# IoTNodeWeatherandWaterAdapterFeb2019v0.net
KiCad netlist of a schematic drawn in EAGLE
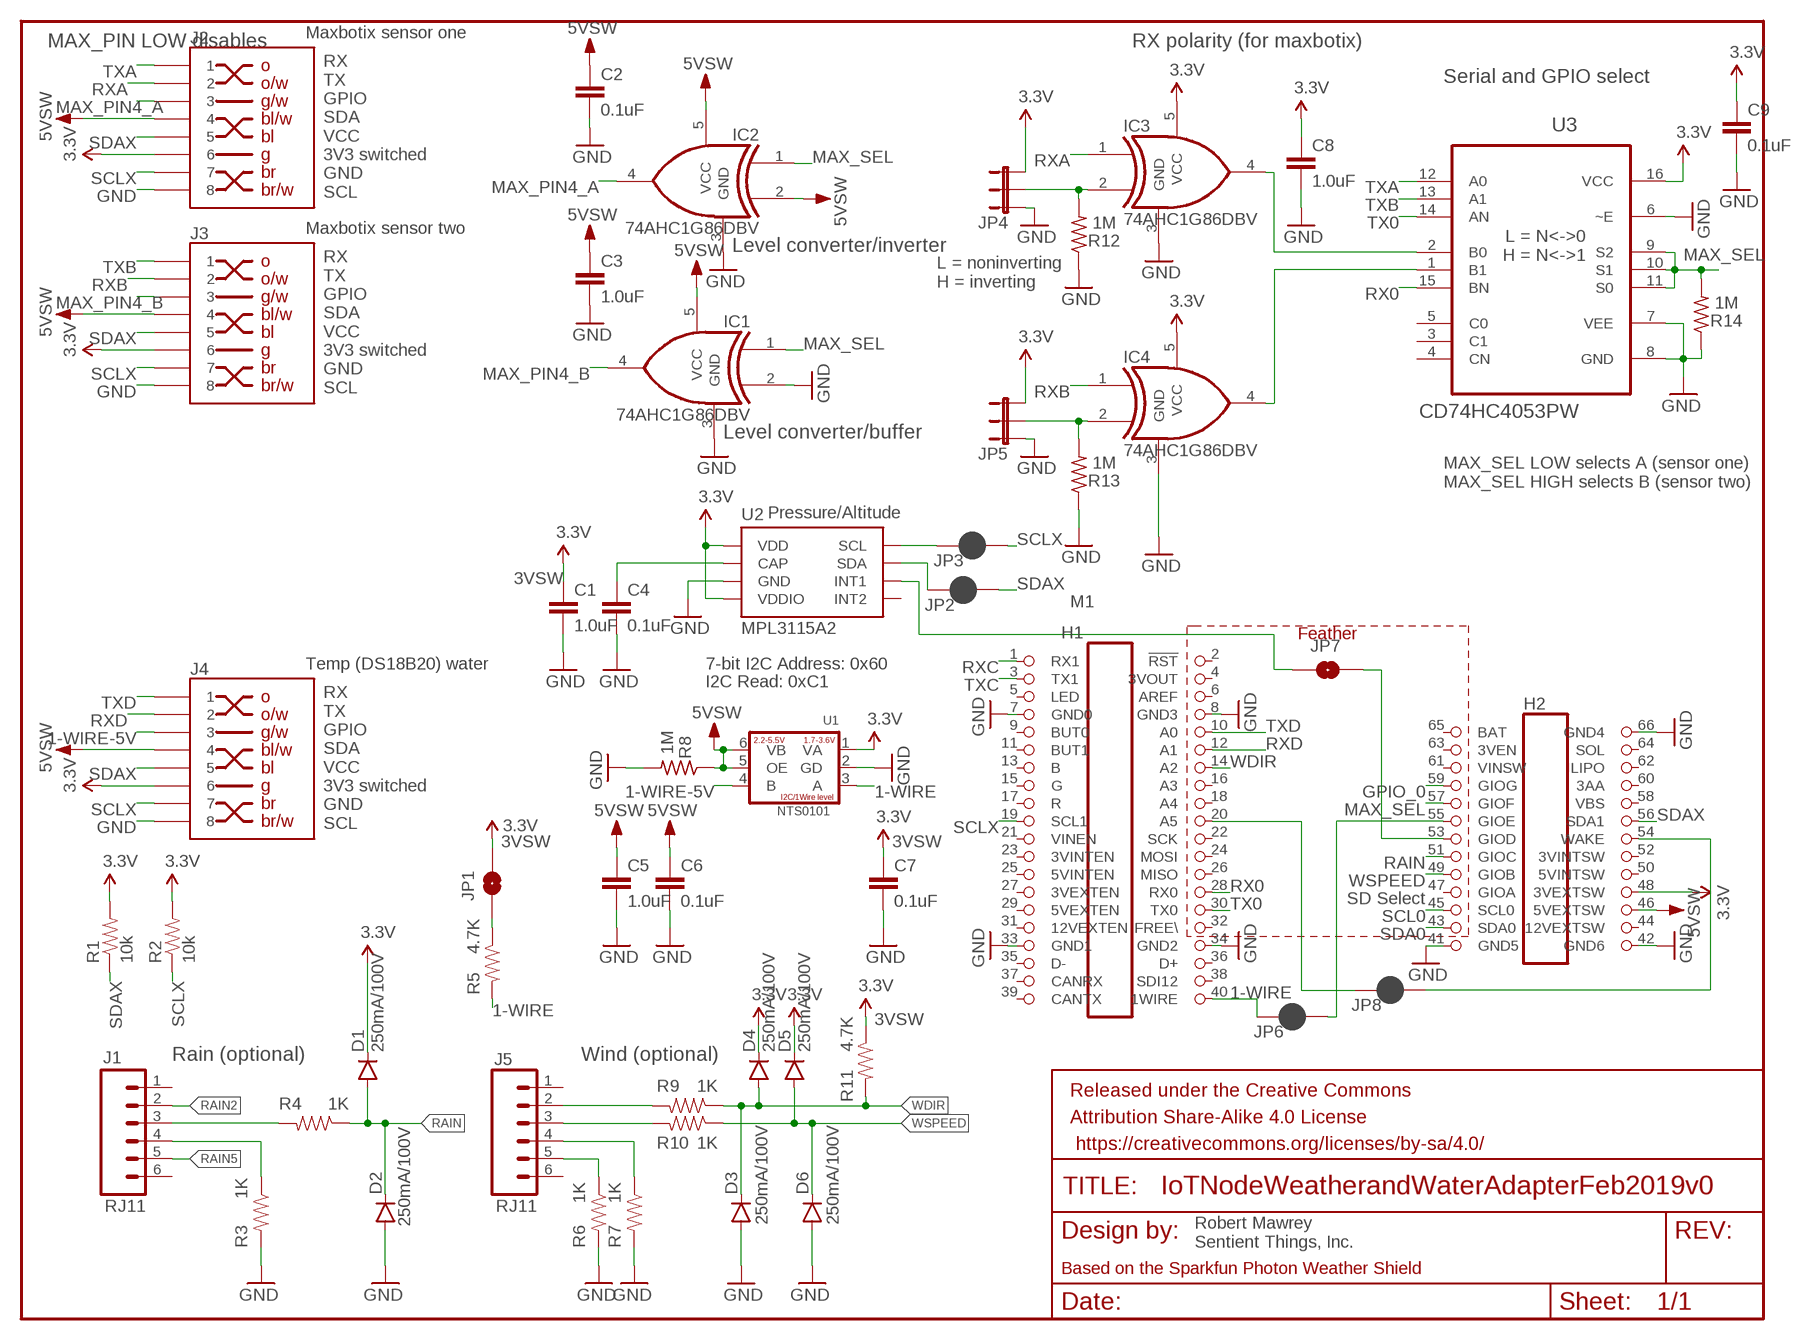
[diagram p0: schematic, sheet 1]

(export (version "E")
  (design (tool "Eeschema 10.0.6"))
  (components
    (comp (ref "C1")
      (value "1.0uF")
      (footprint "eagle-import:0603-CAP")
      (fields (field (name "PARTNO") "CC0603KRX7R8BB105"))
      (libsource (lib "eagle-import") (part "1.0UF-16V-10%(0603)"))
    )
    (comp (ref "C2")
      (value "0.1uF")
      (footprint "eagle-import:0603-CAP")
      (fields (field (name "PARTNO") "C1608X5R1H104K080AA"))
      (libsource (lib "eagle-import") (part "0.1UF-25V(+80/-20%)(0603)"))
    )
    (comp (ref "C3")
      (value "1.0uF")
      (footprint "eagle-import:0603-CAP")
      (fields (field (name "PARTNO") "CC0603KRX7R8BB105"))
      (libsource (lib "eagle-import") (part "1.0UF-16V-10%(0603)"))
    )
    (comp (ref "C4")
      (value "0.1uF")
      (footprint "eagle-import:0603-CAP")
      (fields (field (name "PARTNO") "C1608X5R1H104K080AA"))
      (libsource (lib "eagle-import") (part "0.1UF-25V(+80/-20%)(0603)"))
    )
    (comp (ref "C5")
      (value "1.0uF")
      (footprint "eagle-import:0603-CAP")
      (fields (field (name "PARTNO") "CC0603KRX7R8BB105"))
      (libsource (lib "eagle-import") (part "1.0UF-16V-10%(0603)"))
    )
    (comp (ref "C6")
      (value "0.1uF")
      (footprint "eagle-import:0603-CAP")
      (fields (field (name "PARTNO") "C1608X5R1H104K080AA"))
      (libsource (lib "eagle-import") (part "0.1UF-25V(+80/-20%)(0603)"))
    )
    (comp (ref "C7")
      (value "0.1uF")
      (footprint "eagle-import:0603-CAP")
      (fields (field (name "PARTNO") "C1608X5R1H104K080AA"))
      (libsource (lib "eagle-import") (part "0.1UF-25V(+80/-20%)(0603)"))
    )
    (comp (ref "C8")
      (value "1.0uF")
      (footprint "eagle-import:0603-CAP")
      (fields (field (name "PARTNO") "CC0603KRX7R8BB105"))
      (libsource (lib "eagle-import") (part "1.0UF-16V-10%(0603)"))
    )
    (comp (ref "C9")
      (value "0.1uF")
      (footprint "eagle-import:0603-CAP")
      (fields (field (name "PARTNO") "C1608X5R1H104K080AA"))
      (libsource (lib "eagle-import") (part "0.1UF-25V(+80/-20%)(0603)"))
    )
    (comp (ref "D1")
      (value "250mA/100V")
      (footprint "eagle-import:SOD-323")
      (fields (field (name "PARTNO") "BAS16J,135"))
      (libsource (lib "eagle-import") (part "DIODEBAS16"))
    )
    (comp (ref "D2")
      (value "250mA/100V")
      (footprint "eagle-import:SOD-323")
      (fields (field (name "PARTNO") "BAS16J,135"))
      (libsource (lib "eagle-import") (part "DIODEBAS16"))
    )
    (comp (ref "D3")
      (value "250mA/100V")
      (footprint "eagle-import:SOD-323")
      (fields (field (name "PARTNO") "BAS16J,135"))
      (libsource (lib "eagle-import") (part "DIODEBAS16"))
    )
    (comp (ref "D4")
      (value "250mA/100V")
      (footprint "eagle-import:SOD-323")
      (fields (field (name "PARTNO") "BAS16J,135"))
      (libsource (lib "eagle-import") (part "DIODEBAS16"))
    )
    (comp (ref "D5")
      (value "250mA/100V")
      (footprint "eagle-import:SOD-323")
      (fields (field (name "PARTNO") "BAS16J,135"))
      (libsource (lib "eagle-import") (part "DIODEBAS16"))
    )
    (comp (ref "D6")
      (value "250mA/100V")
      (footprint "eagle-import:SOD-323")
      (fields (field (name "PARTNO") "BAS16J,135"))
      (libsource (lib "eagle-import") (part "DIODEBAS16"))
    )
    (comp (ref "FRAME1")
      (value "FRAME-LETTER")
      (footprint "eagle-import:CREATIVE_COMMONS")
      (fields (field (name "PARTNO") "DNP"))
      (libsource (lib "eagle-import") (part "FRAME-LETTER"))
    )
    (comp (ref "H1")
      (value "IOTNODE2X20PLACEMENT")
      (footprint "eagle-import:2X20PLACEMENT")
      (libsource (lib "eagle-import") (part "IOTNODE2X20PLACEMENT"))
    )
    (comp (ref "H2")
      (value "IOTNODE2X13PLACEMENT")
      (footprint "eagle-import:2X13PLACEMENT")
      (libsource (lib "eagle-import") (part "IOTNODE2X13PLACEMENT"))
    )
    (comp (ref "IC1")
      (value "74AHC1G86DBV")
      (footprint "eagle-import:SOT23-5")
      (fields (field (name "PARTNO") "SN74AHC1G86DBVR"))
      (libsource (lib "eagle-import") (part "741G86DBVAHC"))
    )
    (comp (ref "IC2")
      (value "74AHC1G86DBV")
      (footprint "eagle-import:SOT23-5")
      (fields (field (name "PARTNO") "SN74AHC1G86DBVR"))
      (libsource (lib "eagle-import") (part "741G86DBVAHC"))
    )
    (comp (ref "IC3")
      (value "74AHC1G86DBV")
      (footprint "eagle-import:SOT23-5")
      (fields (field (name "PARTNO") "SN74AHC1G86DBVR"))
      (libsource (lib "eagle-import") (part "741G86DBVAHC"))
    )
    (comp (ref "IC4")
      (value "74AHC1G86DBV")
      (footprint "eagle-import:SOT23-5")
      (fields (field (name "PARTNO") "SN74AHC1G86DBVR"))
      (libsource (lib "eagle-import") (part "741G86DBVAHC"))
    )
    (comp (ref "J1")
      (value "RJ11")
      (footprint "eagle-import:RJ11-6")
      (fields (field (name "PARTNO") "5555165-1"))
      (libsource (lib "eagle-import") (part "RJ11-6PTH"))
    )
    (comp (ref "J2")
      (value "RJ45-8-UP")
      (footprint "eagle-import:RJHSE-5080")
      (fields (field (name "PARTNO") "RJHSE-5080"))
      (libsource (lib "eagle-import") (part "RJ45-8-UP"))
    )
    (comp (ref "J3")
      (value "RJ45-8-UP")
      (footprint "eagle-import:RJHSE-5080")
      (fields (field (name "PARTNO") "RJHSE-5080"))
      (libsource (lib "eagle-import") (part "RJ45-8-UP"))
    )
    (comp (ref "J4")
      (value "RJ45-8-UP")
      (footprint "eagle-import:RJHSE-5080")
      (fields (field (name "PARTNO") "RJHSE-5080"))
      (libsource (lib "eagle-import") (part "RJ45-8-UP"))
    )
    (comp (ref "J5")
      (value "RJ11")
      (footprint "eagle-import:RJ11-6")
      (fields (field (name "PARTNO") "5555165-1"))
      (libsource (lib "eagle-import") (part "RJ11-6PTH"))
    )
    (comp (ref "JP1")
      (value "JUMPER-PAD-2-NOYES_SILK")
      (footprint "eagle-import:PAD-JUMPER-2-NO_YES_SILK")
      (fields (field (name "PARTNO") "DNP"))
      (libsource (lib "eagle-import") (part "JUMPER-PAD-2-NOYES_SILK"))
    )
    (comp (ref "JP2")
      (value "JUMPER-SMT_2_NC_PASTE_NO-SILK")
      (footprint "eagle-import:SMT-JUMPER_2_NC_PASTE_NO-SILK")
      (fields (field (name "PARTNO") "DNP"))
      (libsource (lib "eagle-import") (part "JUMPER-SMT_2_NC_PASTE_NO-SILK"))
    )
    (comp (ref "JP3")
      (value "JUMPER-SMT_2_NC_PASTE_NO-SILK")
      (footprint "eagle-import:SMT-JUMPER_2_NC_PASTE_NO-SILK")
      (fields (field (name "PARTNO") "DNP"))
      (libsource (lib "eagle-import") (part "JUMPER-SMT_2_NC_PASTE_NO-SILK"))
    )
    (comp (ref "JP4")
      (value "JUMPER-3LOCK")
      (footprint "eagle-import:1X03_LOCK")
      (fields (field (name "PARTNO") "68000-103HLF"))
      (libsource (lib "eagle-import") (part "JUMPER-3LOCK"))
    )
    (comp (ref "JP5")
      (value "JUMPER-3LOCK")
      (footprint "eagle-import:1X03_LOCK")
      (fields (field (name "PARTNO") "68000-103HLF"))
      (libsource (lib "eagle-import") (part "JUMPER-3LOCK"))
    )
    (comp (ref "JP6")
      (value "JUMPER-SMT_2_NC_PASTE_NO-SILK")
      (footprint "eagle-import:SMT-JUMPER_2_NC_PASTE_NO-SILK")
      (fields (field (name "PARTNO") "DNP"))
      (libsource (lib "eagle-import") (part "JUMPER-SMT_2_NC_PASTE_NO-SILK"))
    )
    (comp (ref "JP7")
      (value "JUMPER-SMT_2_NO_NO-SILK")
      (footprint "eagle-import:SMT-JUMPER_2_NO_NO-SILK")
      (fields (field (name "PARTNO") "DNP"))
      (libsource (lib "eagle-import") (part "JUMPER-SMT_2_NO_NO-SILK"))
    )
    (comp (ref "JP8")
      (value "JUMPER-SMT_2_NC_PASTE_NO-SILK")
      (footprint "eagle-import:SMT-JUMPER_2_NC_PASTE_NO-SILK")
      (fields (field (name "PARTNO") "DNP"))
      (libsource (lib "eagle-import") (part "JUMPER-SMT_2_NC_PASTE_NO-SILK"))
    )
    (comp (ref "M1")
      (value "IOTNODEFEATHERWING")
      (footprint "eagle-import:IOTNODEFEATHERWING")
      (fields (field (name "PARTNO") "DNP"))
      (libsource (lib "eagle-import") (part "IOTNODEFEATHERWING"))
    )
    (comp (ref "R1")
      (value "10k")
      (footprint "eagle-import:0603-RES")
      (fields (field (name "PARTNO") "ERJ-3GEYJ103V"))
      (libsource (lib "eagle-import") (part "RESISTOR0603-RES"))
    )
    (comp (ref "R2")
      (value "10k")
      (footprint "eagle-import:0603-RES")
      (fields (field (name "PARTNO") "ERJ-3GEYJ103V"))
      (libsource (lib "eagle-import") (part "RESISTOR0603-RES"))
    )
    (comp (ref "R3")
      (value "1K")
      (footprint "eagle-import:0603-RES")
      (fields (field (name "PARTNO") "RC0603JR-071KL"))
      (libsource (lib "eagle-import") (part "1KOHM-1/10W-1%(0603)"))
    )
    (comp (ref "R4")
      (value "1K")
      (footprint "eagle-import:0603-RES")
      (fields (field (name "PARTNO") "RC0603JR-071KL"))
      (libsource (lib "eagle-import") (part "1KOHM-1/10W-1%(0603)"))
    )
    (comp (ref "R5")
      (value "4.7K")
      (footprint "eagle-import:0603-RES")
      (fields (field (name "PARTNO") "RC0603JR-074K7L"))
      (libsource (lib "eagle-import") (part "4.7KOHM-1/10W-1%(0603)"))
    )
    (comp (ref "R6")
      (value "1K")
      (footprint "eagle-import:0603-RES")
      (fields (field (name "PARTNO") "RC0603JR-071KL"))
      (libsource (lib "eagle-import") (part "1KOHM-1/10W-1%(0603)"))
    )
    (comp (ref "R7")
      (value "1K")
      (footprint "eagle-import:0603-RES")
      (fields (field (name "PARTNO") "RC0603JR-071KL"))
      (libsource (lib "eagle-import") (part "1KOHM-1/10W-1%(0603)"))
    )
    (comp (ref "R8")
      (value "1M")
      (footprint "eagle-import:0603")
      (fields (field (name "PARTNO") "RC0603FR-071ML"))
      (libsource (lib "eagle-import") (part "R_0603"))
    )
    (comp (ref "R9")
      (value "1K")
      (footprint "eagle-import:0603-RES")
      (fields (field (name "PARTNO") "RC0603JR-071KL"))
      (libsource (lib "eagle-import") (part "1KOHM-1/10W-1%(0603)"))
    )
    (comp (ref "R10")
      (value "1K")
      (footprint "eagle-import:0603-RES")
      (fields (field (name "PARTNO") "RC0603JR-071KL"))
      (libsource (lib "eagle-import") (part "1KOHM-1/10W-1%(0603)"))
    )
    (comp (ref "R11")
      (value "4.7K")
      (footprint "eagle-import:0603-RES")
      (fields (field (name "PARTNO") "RC0603JR-074K7L"))
      (libsource (lib "eagle-import") (part "4.7KOHM-1/10W-1%(0603)"))
    )
    (comp (ref "R12")
      (value "1M")
      (footprint "eagle-import:0603")
      (fields (field (name "PARTNO") "RC0603FR-071ML"))
      (libsource (lib "eagle-import") (part "R_0603"))
    )
    (comp (ref "R13")
      (value "1M")
      (footprint "eagle-import:0603")
      (fields (field (name "PARTNO") "RC0603FR-071ML"))
      (libsource (lib "eagle-import") (part "R_0603"))
    )
    (comp (ref "R14")
      (value "1M")
      (footprint "eagle-import:0603")
      (fields (field (name "PARTNO") "RC0603FR-071ML"))
      (libsource (lib "eagle-import") (part "R_0603"))
    )
    (comp (ref "U1")
      (value "NTS0101")
      (footprint "eagle-import:SOT363_PHILIPS")
      (fields (field (name "PARTNO") "NTS0101GW,125"))
      (libsource (lib "eagle-import") (part "NTS0101-SC-88"))
    )
    (comp (ref "U2")
      (value "MPL3115A2")
      (footprint "eagle-import:LGA-8-5X3")
      (libsource (lib "eagle-import") (part "MPL3115A2"))
    )
    (comp (ref "U3")
      (value "CD74HC4053PW")
      (footprint "eagle-import:SOP65P640X120-16N")
      (fields (field (name "PARTNO") "74HC4053PW,118"))
      (libsource (lib "eagle-import") (part "CD74HC4053PW"))
    )
  )
  (nets
    (net (code "1") (name "/1-WIRE") (class "Default")
      (node (ref "JP6") (pin "2") (pinfunction "2_2") (pintype "passive"))
      (node (ref "M1") (pin "40") (pinfunction "1WIRE_40") (pintype "bidirectional"))
      (node (ref "R5") (pin "2") (pinfunction "2_2") (pintype "passive"))
      (node (ref "U1") (pin "3") (pinfunction "A_3") (pintype "bidirectional"))
    )
    (net (code "2") (name "/1-WIRE-5V") (class "Default")
      (node (ref "J4") (pin "3") (pinfunction "3_3") (pintype "bidirectional"))
      (node (ref "U1") (pin "4") (pinfunction "B_4") (pintype "bidirectional"))
    )
    (net (code "3") (name "/GPIO_0") (class "Default")
      (node (ref "M1") (pin "59") (pinfunction "GIOG_59") (pintype "bidirectional"))
    )
    (net (code "4") (name "/MAX_PIN4_A") (class "Default")
      (node (ref "IC2") (pin "4") (pinfunction "O_4") (pintype "output"))
      (node (ref "J2") (pin "3") (pinfunction "3_3") (pintype "bidirectional"))
    )
    (net (code "5") (name "/MAX_PIN4_B") (class "Default")
      (node (ref "IC1") (pin "4") (pinfunction "O_4") (pintype "output"))
      (node (ref "J3") (pin "3") (pinfunction "3_3") (pintype "bidirectional"))
    )
    (net (code "6") (name "/MAX_SEL") (class "Default")
      (node (ref "IC1") (pin "1") (pinfunction "I0_1") (pintype "input"))
      (node (ref "IC2") (pin "1") (pinfunction "I0_1") (pintype "input"))
      (node (ref "M1") (pin "57") (pinfunction "GIOF_57") (pintype "bidirectional"))
      (node (ref "R14") (pin "2") (pinfunction "2_2") (pintype "passive"))
      (node (ref "U3") (pin "10") (pinfunction "S1_10") (pintype "input"))
      (node (ref "U3") (pin "11") (pinfunction "S0_11") (pintype "input"))
      (node (ref "U3") (pin "9") (pinfunction "S2_9") (pintype "input"))
    )
    (net (code "7") (name "/RX0") (class "Default")
      (node (ref "M1") (pin "28") (pinfunction "RX0_28") (pintype "bidirectional"))
      (node (ref "U3") (pin "15") (pinfunction "BN_15") (pintype "output"))
    )
    (net (code "8") (name "/RXA") (class "Default")
      (node (ref "IC3") (pin "1") (pinfunction "I0_1") (pintype "input"))
      (node (ref "J2") (pin "2") (pinfunction "2_2") (pintype "bidirectional"))
    )
    (net (code "9") (name "/RXB") (class "Default")
      (node (ref "IC4") (pin "1") (pinfunction "I0_1") (pintype "input"))
      (node (ref "J3") (pin "2") (pinfunction "2_2") (pintype "bidirectional"))
    )
    (net (code "10") (name "/RXC") (class "Default")
      (node (ref "M1") (pin "1") (pinfunction "RX1_1") (pintype "bidirectional"))
    )
    (net (code "11") (name "/RXD") (class "Default")
      (node (ref "J4") (pin "2") (pinfunction "2_2") (pintype "bidirectional"))
      (node (ref "M1") (pin "12") (pinfunction "A1_12") (pintype "bidirectional"))
    )
    (net (code "12") (name "/SCL0") (class "Default")
      (node (ref "M1") (pin "45") (pinfunction "SCL0_45") (pintype "bidirectional"))
    )
    (net (code "13") (name "/SCLX") (class "Default")
      (node (ref "J2") (pin "7") (pinfunction "7_7") (pintype "bidirectional"))
      (node (ref "J3") (pin "7") (pinfunction "7_7") (pintype "bidirectional"))
      (node (ref "J4") (pin "7") (pinfunction "7_7") (pintype "bidirectional"))
      (node (ref "JP3") (pin "1") (pinfunction "1_1") (pintype "passive"))
      (node (ref "M1") (pin "19") (pinfunction "SCL1_19") (pintype "bidirectional"))
      (node (ref "R2") (pin "1") (pinfunction "1_1") (pintype "passive"))
    )
    (net (code "14") (name "/SDA0") (class "Default")
      (node (ref "M1") (pin "43") (pinfunction "SDA0_43") (pintype "bidirectional"))
    )
    (net (code "15") (name "/SDAX") (class "Default")
      (node (ref "J2") (pin "5") (pinfunction "5_5") (pintype "bidirectional"))
      (node (ref "J3") (pin "5") (pinfunction "5_5") (pintype "bidirectional"))
      (node (ref "J4") (pin "5") (pinfunction "5_5") (pintype "bidirectional"))
      (node (ref "JP2") (pin "1") (pinfunction "1_1") (pintype "passive"))
      (node (ref "M1") (pin "56") (pinfunction "SDA1_56") (pintype "bidirectional"))
      (node (ref "R1") (pin "1") (pinfunction "1_1") (pintype "passive"))
    )
    (net (code "16") (name "/TX0") (class "Default")
      (node (ref "M1") (pin "30") (pinfunction "TX0_30") (pintype "bidirectional"))
      (node (ref "U3") (pin "14") (pinfunction "AN_14") (pintype "output"))
    )
    (net (code "17") (name "/TXA") (class "Default")
      (node (ref "J2") (pin "1") (pinfunction "1_1") (pintype "bidirectional"))
      (node (ref "U3") (pin "12") (pinfunction "A0_12") (pintype "output"))
    )
    (net (code "18") (name "/TXB") (class "Default")
      (node (ref "J3") (pin "1") (pinfunction "1_1") (pintype "bidirectional"))
      (node (ref "U3") (pin "13") (pinfunction "A1_13") (pintype "output"))
    )
    (net (code "19") (name "/TXC") (class "Default")
      (node (ref "M1") (pin "3") (pinfunction "TX1_3") (pintype "bidirectional"))
    )
    (net (code "20") (name "/TXD") (class "Default")
      (node (ref "J4") (pin "1") (pinfunction "1_1") (pintype "bidirectional"))
      (node (ref "M1") (pin "10") (pinfunction "A0_10") (pintype "bidirectional"))
    )
    (net (code "21") (name "3.3V") (class "Default")
      (node (ref "C1") (pin "1") (pinfunction "1_1") (pintype "passive"))
      (node (ref "C7") (pin "1") (pinfunction "1_1") (pintype "passive"))
      (node (ref "C8") (pin "1") (pinfunction "1_1") (pintype "passive"))
      (node (ref "C9") (pin "1") (pinfunction "1_1") (pintype "passive"))
      (node (ref "D1") (pin "C") (pinfunction "C_C") (pintype "passive"))
      (node (ref "D4") (pin "C") (pinfunction "C_C") (pintype "passive"))
      (node (ref "D5") (pin "C") (pinfunction "C_C") (pintype "passive"))
      (node (ref "IC3") (pin "5") (pinfunction "VCC_5") (pintype "bidirectional"))
      (node (ref "IC4") (pin "5") (pinfunction "VCC_5") (pintype "bidirectional"))
      (node (ref "J2") (pin "6") (pinfunction "6_6") (pintype "bidirectional"))
      (node (ref "J3") (pin "6") (pinfunction "6_6") (pintype "bidirectional"))
      (node (ref "J4") (pin "6") (pinfunction "6_6") (pintype "bidirectional"))
      (node (ref "JP1") (pin "2") (pinfunction "2_2") (pintype "passive"))
      (node (ref "JP4") (pin "3") (pinfunction "3_3") (pintype "passive"))
      (node (ref "JP5") (pin "3") (pinfunction "3_3") (pintype "passive"))
      (node (ref "M1") (pin "48") (pinfunction "3VEXTSW_48") (pintype "bidirectional"))
      (node (ref "R1") (pin "2") (pinfunction "2_2") (pintype "passive"))
      (node (ref "R11") (pin "1") (pinfunction "1_1") (pintype "passive"))
      (node (ref "R2") (pin "2") (pinfunction "2_2") (pintype "passive"))
      (node (ref "U1") (pin "1") (pinfunction "VA_1") (pintype "bidirectional"))
      (node (ref "U2") (pin "1") (pinfunction "VDD_1") (pintype "power_in"))
      (node (ref "U2") (pin "4") (pinfunction "VDDIO_4") (pintype "power_in"))
      (node (ref "U3") (pin "16") (pinfunction "VCC_16") (pintype "power_in"))
    )
    (net (code "22") (name "5VSW") (class "Default")
      (node (ref "C2") (pin "1") (pinfunction "1_1") (pintype "passive"))
      (node (ref "C3") (pin "1") (pinfunction "1_1") (pintype "passive"))
      (node (ref "C5") (pin "1") (pinfunction "1_1") (pintype "passive"))
      (node (ref "C6") (pin "1") (pinfunction "1_1") (pintype "passive"))
      (node (ref "IC1") (pin "5") (pinfunction "VCC_5") (pintype "bidirectional"))
      (node (ref "IC2") (pin "2") (pinfunction "I1_2") (pintype "input"))
      (node (ref "IC2") (pin "5") (pinfunction "VCC_5") (pintype "bidirectional"))
      (node (ref "J2") (pin "4") (pinfunction "4_4") (pintype "bidirectional"))
      (node (ref "J3") (pin "4") (pinfunction "4_4") (pintype "bidirectional"))
      (node (ref "J4") (pin "4") (pinfunction "4_4") (pintype "bidirectional"))
      (node (ref "M1") (pin "46") (pinfunction "5VEXTSW_46") (pintype "bidirectional"))
      (node (ref "R8") (pin "1") (pinfunction "1_1") (pintype "passive"))
      (node (ref "U1") (pin "5") (pinfunction "OE_5") (pintype "bidirectional"))
      (node (ref "U1") (pin "6") (pinfunction "VB_6") (pintype "bidirectional"))
    )
    (net (code "23") (name "GND") (class "Default")
      (node (ref "C1") (pin "2") (pinfunction "2_2") (pintype "passive"))
      (node (ref "C2") (pin "2") (pinfunction "2_2") (pintype "passive"))
      (node (ref "C3") (pin "2") (pinfunction "2_2") (pintype "passive"))
      (node (ref "C4") (pin "2") (pinfunction "2_2") (pintype "passive"))
      (node (ref "C5") (pin "2") (pinfunction "2_2") (pintype "passive"))
      (node (ref "C6") (pin "2") (pinfunction "2_2") (pintype "passive"))
      (node (ref "C7") (pin "2") (pinfunction "2_2") (pintype "passive"))
      (node (ref "C8") (pin "2") (pinfunction "2_2") (pintype "passive"))
      (node (ref "C9") (pin "2") (pinfunction "2_2") (pintype "passive"))
      (node (ref "D2") (pin "A") (pinfunction "A_A") (pintype "passive"))
      (node (ref "D3") (pin "A") (pinfunction "A_A") (pintype "passive"))
      (node (ref "D6") (pin "A") (pinfunction "A_A") (pintype "passive"))
      (node (ref "IC1") (pin "2") (pinfunction "I1_2") (pintype "input"))
      (node (ref "IC1") (pin "3") (pinfunction "GND_3") (pintype "bidirectional"))
      (node (ref "IC2") (pin "3") (pinfunction "GND_3") (pintype "bidirectional"))
      (node (ref "IC3") (pin "3") (pinfunction "GND_3") (pintype "bidirectional"))
      (node (ref "IC4") (pin "3") (pinfunction "GND_3") (pintype "bidirectional"))
      (node (ref "J2") (pin "8") (pinfunction "8_8") (pintype "bidirectional"))
      (node (ref "J3") (pin "8") (pinfunction "8_8") (pintype "bidirectional"))
      (node (ref "J4") (pin "8") (pinfunction "8_8") (pintype "bidirectional"))
      (node (ref "JP4") (pin "1") (pinfunction "1_1") (pintype "passive"))
      (node (ref "JP5") (pin "1") (pinfunction "1_1") (pintype "passive"))
      (node (ref "M1") (pin "33") (pinfunction "GND1_33") (pintype "bidirectional"))
      (node (ref "M1") (pin "34") (pinfunction "GND2_34") (pintype "bidirectional"))
      (node (ref "M1") (pin "41") (pinfunction "GND5_41") (pintype "bidirectional"))
      (node (ref "M1") (pin "42") (pinfunction "GND6_42") (pintype "bidirectional"))
      (node (ref "M1") (pin "66") (pinfunction "GND4_66") (pintype "bidirectional"))
      (node (ref "M1") (pin "7") (pinfunction "GND0_7") (pintype "bidirectional"))
      (node (ref "M1") (pin "8") (pinfunction "GND3_8") (pintype "bidirectional"))
      (node (ref "R12") (pin "1") (pinfunction "1_1") (pintype "passive"))
      (node (ref "R13") (pin "1") (pinfunction "1_1") (pintype "passive"))
      (node (ref "R14") (pin "1") (pinfunction "1_1") (pintype "passive"))
      (node (ref "R3") (pin "2") (pinfunction "2_2") (pintype "passive"))
      (node (ref "R6") (pin "2") (pinfunction "2_2") (pintype "passive"))
      (node (ref "R7") (pin "2") (pinfunction "2_2") (pintype "passive"))
      (node (ref "R8") (pin "2") (pinfunction "2_2") (pintype "passive"))
      (node (ref "U1") (pin "2") (pinfunction "GD_2") (pintype "bidirectional"))
      (node (ref "U2") (pin "3") (pinfunction "GND_3") (pintype "power_in"))
      (node (ref "U3") (pin "6") (pinfunction "~{E}_6") (pintype "input"))
      (node (ref "U3") (pin "7") (pinfunction "VEE_7") (pintype "power_in"))
      (node (ref "U3") (pin "8") (pinfunction "GND_8") (pintype "passive"))
    )
    (net (code "24") (name "Net-(IC3-I1)") (class "Default")
      (node (ref "IC3") (pin "2") (pinfunction "I1_2") (pintype "input"))
      (node (ref "JP4") (pin "2") (pinfunction "2_2") (pintype "passive"))
      (node (ref "R12") (pin "2") (pinfunction "2_2") (pintype "passive"))
    )
    (net (code "25") (name "Net-(IC3-O)") (class "Default")
      (node (ref "IC3") (pin "4") (pinfunction "O_4") (pintype "output"))
      (node (ref "U3") (pin "2") (pinfunction "B0_2") (pintype "output"))
    )
    (net (code "26") (name "Net-(IC4-I1)") (class "Default")
      (node (ref "IC4") (pin "2") (pinfunction "I1_2") (pintype "input"))
      (node (ref "JP5") (pin "2") (pinfunction "2_2") (pintype "passive"))
      (node (ref "R13") (pin "2") (pinfunction "2_2") (pintype "passive"))
    )
    (net (code "27") (name "Net-(IC4-O)") (class "Default")
      (node (ref "IC4") (pin "4") (pinfunction "O_4") (pintype "output"))
      (node (ref "U3") (pin "1") (pinfunction "B1_1") (pintype "output"))
    )
    (net (code "28") (name "Net-(J1-Pad3)") (class "Default")
      (node (ref "J1") (pin "3") (pinfunction "3_3") (pintype "passive"))
      (node (ref "R4") (pin "2") (pinfunction "2_2") (pintype "passive"))
    )
    (net (code "29") (name "Net-(J1-Pad4)") (class "Default")
      (node (ref "J1") (pin "4") (pinfunction "4_4") (pintype "passive"))
      (node (ref "R3") (pin "1") (pinfunction "1_1") (pintype "passive"))
    )
    (net (code "30") (name "Net-(J5-Pad2)") (class "Default")
      (node (ref "J5") (pin "2") (pinfunction "2_2") (pintype "passive"))
      (node (ref "R9") (pin "2") (pinfunction "2_2") (pintype "passive"))
    )
    (net (code "31") (name "Net-(J5-Pad3)") (class "Default")
      (node (ref "J5") (pin "3") (pinfunction "3_3") (pintype "passive"))
      (node (ref "R10") (pin "2") (pinfunction "2_2") (pintype "passive"))
    )
    (net (code "32") (name "Net-(J5-Pad4)") (class "Default")
      (node (ref "J5") (pin "4") (pinfunction "4_4") (pintype "passive"))
      (node (ref "R7") (pin "1") (pinfunction "1_1") (pintype "passive"))
    )
    (net (code "33") (name "Net-(J5-Pad5)") (class "Default")
      (node (ref "J5") (pin "5") (pinfunction "5_5") (pintype "passive"))
      (node (ref "R6") (pin "1") (pinfunction "1_1") (pintype "passive"))
    )
    (net (code "34") (name "Net-(JP1-Pad1)") (class "Default")
      (node (ref "JP1") (pin "1") (pinfunction "1_1") (pintype "passive"))
      (node (ref "R5") (pin "1") (pinfunction "1_1") (pintype "passive"))
    )
    (net (code "35") (name "Net-(M1-A5)") (class "Default")
      (node (ref "JP8") (pin "2") (pinfunction "2_2") (pintype "passive"))
      (node (ref "M1") (pin "20") (pinfunction "A5_20") (pintype "bidirectional"))
    )
    (net (code "36") (name "Net-(M1-GIOD)") (class "Default")
      (node (ref "JP7") (pin "2") (pinfunction "2_2") (pintype "passive"))
      (node (ref "M1") (pin "53") (pinfunction "GIOD_53") (pintype "bidirectional"))
    )
    (net (code "37") (name "Net-(M1-GIOE)") (class "Default")
      (node (ref "JP6") (pin "1") (pinfunction "1_1") (pintype "passive"))
      (node (ref "M1") (pin "55") (pinfunction "GIOE_55") (pintype "bidirectional"))
    )
    (net (code "38") (name "Net-(M1-WAKE)") (class "Default")
      (node (ref "JP8") (pin "1") (pinfunction "1_1") (pintype "passive"))
      (node (ref "M1") (pin "54") (pinfunction "WAKE_54") (pintype "bidirectional"))
    )
    (net (code "39") (name "Net-(U2-CAP)") (class "Default")
      (node (ref "C4") (pin "1") (pinfunction "1_1") (pintype "passive"))
      (node (ref "U2") (pin "2") (pinfunction "CAP_2") (pintype "power_in"))
    )
    (net (code "40") (name "Net-(U2-INT1)") (class "Default")
      (node (ref "JP7") (pin "1") (pinfunction "1_1") (pintype "passive"))
      (node (ref "U2") (pin "6") (pinfunction "INT1_6") (pintype "output"))
    )
    (net (code "41") (name "Net-(U2-SCL)") (class "Default")
      (node (ref "JP3") (pin "2") (pinfunction "2_2") (pintype "passive"))
      (node (ref "U2") (pin "8") (pinfunction "SCL_8") (pintype "bidirectional"))
    )
    (net (code "42") (name "Net-(U2-SDA)") (class "Default")
      (node (ref "JP2") (pin "2") (pinfunction "2_2") (pintype "passive"))
      (node (ref "U2") (pin "7") (pinfunction "SDA_7") (pintype "bidirectional"))
    )
    (net (code "43") (name "RAIN") (class "Default")
      (node (ref "D1") (pin "A") (pinfunction "A_A") (pintype "passive"))
      (node (ref "D2") (pin "C") (pinfunction "C_C") (pintype "passive"))
      (node (ref "M1") (pin "51") (pinfunction "GIOC_51") (pintype "bidirectional"))
      (node (ref "R4") (pin "1") (pinfunction "1_1") (pintype "passive"))
    )
    (net (code "44") (name "RAIN2") (class "Default")
      (node (ref "J1") (pin "2") (pinfunction "2_2") (pintype "passive"))
    )
    (net (code "45") (name "RAIN5") (class "Default")
      (node (ref "J1") (pin "5") (pinfunction "5_5") (pintype "passive"))
    )
    (net (code "46") (name "WDIR") (class "Default")
      (node (ref "D3") (pin "C") (pinfunction "C_C") (pintype "passive"))
      (node (ref "D4") (pin "A") (pinfunction "A_A") (pintype "passive"))
      (node (ref "M1") (pin "14") (pinfunction "A2_14") (pintype "bidirectional"))
      (node (ref "R11") (pin "2") (pinfunction "2_2") (pintype "passive"))
      (node (ref "R9") (pin "1") (pinfunction "1_1") (pintype "passive"))
    )
    (net (code "47") (name "WSPEED") (class "Default")
      (node (ref "D5") (pin "A") (pinfunction "A_A") (pintype "passive"))
      (node (ref "D6") (pin "C") (pinfunction "C_C") (pintype "passive"))
      (node (ref "M1") (pin "49") (pinfunction "GIOB_49") (pintype "bidirectional"))
      (node (ref "R10") (pin "1") (pinfunction "1_1") (pintype "passive"))
    )
    (net (code "48") (name "unconnected-(J1-Pad1)") (class "Default")
      (node (ref "J1") (pin "1") (pinfunction "1_1") (pintype "passive"))
    )
    (net (code "49") (name "unconnected-(J1-Pad6)") (class "Default")
      (node (ref "J1") (pin "6") (pinfunction "6_6") (pintype "passive"))
    )
    (net (code "50") (name "unconnected-(J5-Pad1)") (class "Default")
      (node (ref "J5") (pin "1") (pinfunction "1_1") (pintype "passive"))
    )
    (net (code "51") (name "unconnected-(J5-Pad6)") (class "Default")
      (node (ref "J5") (pin "6") (pinfunction "6_6") (pintype "passive"))
    )
    (net (code "52") (name "unconnected-(M1-3AA-Pad60)") (class "Default")
      (node (ref "M1") (pin "60") (pinfunction "3AA_60") (pintype "bidirectional"))
    )
    (net (code "53") (name "unconnected-(M1-3VEN-Pad63)") (class "Default")
      (node (ref "M1") (pin "63") (pinfunction "3VEN_63") (pintype "bidirectional"))
    )
    (net (code "54") (name "unconnected-(M1-3VEXTEN-Pad27)") (class "Default")
      (node (ref "M1") (pin "27") (pinfunction "3VEXTEN_27") (pintype "bidirectional"))
    )
    (net (code "55") (name "unconnected-(M1-3VINTEN-Pad23)") (class "Default")
      (node (ref "M1") (pin "23") (pinfunction "3VINTEN_23") (pintype "bidirectional"))
    )
    (net (code "56") (name "unconnected-(M1-3VINTSW-Pad52)") (class "Default")
      (node (ref "M1") (pin "52") (pinfunction "3VINTSW_52") (pintype "bidirectional"))
    )
    (net (code "57") (name "unconnected-(M1-3VOUT-Pad4)") (class "Default")
      (node (ref "M1") (pin "4") (pinfunction "3VOUT_4") (pintype "bidirectional"))
    )
    (net (code "58") (name "unconnected-(M1-5VEXTEN-Pad29)") (class "Default")
      (node (ref "M1") (pin "29") (pinfunction "5VEXTEN_29") (pintype "bidirectional"))
    )
    (net (code "59") (name "unconnected-(M1-5VINTEN-Pad25)") (class "Default")
      (node (ref "M1") (pin "25") (pinfunction "5VINTEN_25") (pintype "bidirectional"))
    )
    (net (code "60") (name "unconnected-(M1-5VINTSW-Pad50)") (class "Default")
      (node (ref "M1") (pin "50") (pinfunction "5VINTSW_50") (pintype "bidirectional"))
    )
    (net (code "61") (name "unconnected-(M1-12VEXTEN-Pad31)") (class "Default")
      (node (ref "M1") (pin "31") (pinfunction "12VEXTEN_31") (pintype "bidirectional"))
    )
    (net (code "62") (name "unconnected-(M1-12VEXTSW-Pad44)") (class "Default")
      (node (ref "M1") (pin "44") (pinfunction "12VEXTSW_44") (pintype "bidirectional"))
    )
    (net (code "63") (name "unconnected-(M1-A3-Pad16)") (class "Default")
      (node (ref "M1") (pin "16") (pinfunction "A3_16") (pintype "bidirectional"))
    )
    (net (code "64") (name "unconnected-(M1-A4-Pad18)") (class "Default")
      (node (ref "M1") (pin "18") (pinfunction "A4_18") (pintype "bidirectional"))
    )
    (net (code "65") (name "unconnected-(M1-AREF-Pad6)") (class "Default")
      (node (ref "M1") (pin "6") (pinfunction "AREF_6") (pintype "bidirectional"))
    )
    (net (code "66") (name "unconnected-(M1-B-Pad13)") (class "Default")
      (node (ref "M1") (pin "13") (pinfunction "B_13") (pintype "bidirectional"))
    )
    (net (code "67") (name "unconnected-(M1-BAT-Pad65)") (class "Default")
      (node (ref "M1") (pin "65") (pinfunction "BAT_65") (pintype "bidirectional"))
    )
    (net (code "68") (name "unconnected-(M1-BUT0-Pad9)") (class "Default")
      (node (ref "M1") (pin "9") (pinfunction "BUT0_9") (pintype "bidirectional"))
    )
    (net (code "69") (name "unconnected-(M1-BUT1-Pad11)") (class "Default")
      (node (ref "M1") (pin "11") (pinfunction "BUT1_11") (pintype "bidirectional"))
    )
    (net (code "70") (name "unconnected-(M1-CANRX-Pad37)") (class "Default")
      (node (ref "M1") (pin "37") (pinfunction "CANRX_37") (pintype "bidirectional"))
    )
    (net (code "71") (name "unconnected-(M1-CANTX-Pad39)") (class "Default")
      (node (ref "M1") (pin "39") (pinfunction "CANTX_39") (pintype "bidirectional"))
    )
    (net (code "72") (name "unconnected-(M1-D+-Pad36)") (class "Default")
      (node (ref "M1") (pin "36") (pinfunction "D+_36") (pintype "bidirectional"))
    )
    (net (code "73") (name "unconnected-(M1-D--Pad35)") (class "Default")
      (node (ref "M1") (pin "35") (pinfunction "D-_35") (pintype "bidirectional"))
    )
    (net (code "74") (name "unconnected-(M1-FREE\\-Pad32)") (class "Default")
      (node (ref "M1") (pin "32") (pinfunction "FREE\\_32") (pintype "bidirectional"))
    )
    (net (code "75") (name "unconnected-(M1-G-Pad15)") (class "Default")
      (node (ref "M1") (pin "15") (pinfunction "G_15") (pintype "bidirectional"))
    )
    (net (code "76") (name "unconnected-(M1-GIOA-Pad47)") (class "Default")
      (node (ref "M1") (pin "47") (pinfunction "GIOA_47") (pintype "bidirectional"))
    )
    (net (code "77") (name "unconnected-(M1-LED-Pad5)") (class "Default")
      (node (ref "M1") (pin "5") (pinfunction "LED_5") (pintype "bidirectional"))
    )
    (net (code "78") (name "unconnected-(M1-LIPO-Pad62)") (class "Default")
      (node (ref "M1") (pin "62") (pinfunction "LIPO_62") (pintype "bidirectional"))
    )
    (net (code "79") (name "unconnected-(M1-MISO-Pad26)") (class "Default")
      (node (ref "M1") (pin "26") (pinfunction "MISO_26") (pintype "bidirectional"))
    )
    (net (code "80") (name "unconnected-(M1-MOSI-Pad24)") (class "Default")
      (node (ref "M1") (pin "24") (pinfunction "MOSI_24") (pintype "bidirectional"))
    )
    (net (code "81") (name "unconnected-(M1-R-Pad17)") (class "Default")
      (node (ref "M1") (pin "17") (pinfunction "R_17") (pintype "bidirectional"))
    )
    (net (code "82") (name "unconnected-(M1-SCK-Pad22)") (class "Default")
      (node (ref "M1") (pin "22") (pinfunction "SCK_22") (pintype "bidirectional"))
    )
    (net (code "83") (name "unconnected-(M1-SDI12-Pad38)") (class "Default")
      (node (ref "M1") (pin "38") (pinfunction "SDI12_38") (pintype "bidirectional"))
    )
    (net (code "84") (name "unconnected-(M1-SOL-Pad64)") (class "Default")
      (node (ref "M1") (pin "64") (pinfunction "SOL_64") (pintype "bidirectional"))
    )
    (net (code "85") (name "unconnected-(M1-VBS-Pad58)") (class "Default")
      (node (ref "M1") (pin "58") (pinfunction "VBS_58") (pintype "bidirectional"))
    )
    (net (code "86") (name "unconnected-(M1-VINEN-Pad21)") (class "Default")
      (node (ref "M1") (pin "21") (pinfunction "VINEN_21") (pintype "bidirectional"))
    )
    (net (code "87") (name "unconnected-(M1-VINSW-Pad61)") (class "Default")
      (node (ref "M1") (pin "61") (pinfunction "VINSW_61") (pintype "bidirectional"))
    )
    (net (code "88") (name "unconnected-(M1-~{RST}-Pad2)") (class "Default")
      (node (ref "M1") (pin "2") (pinfunction "~{RST}_2") (pintype "bidirectional"))
    )
    (net (code "89") (name "unconnected-(U2-INT2-Pad5)") (class "Default")
      (node (ref "U2") (pin "5") (pinfunction "INT2_5") (pintype "output"))
    )
    (net (code "90") (name "unconnected-(U3-C0-Pad5)") (class "Default")
      (node (ref "U3") (pin "5") (pinfunction "C0_5") (pintype "output"))
    )
    (net (code "91") (name "unconnected-(U3-C1-Pad3)") (class "Default")
      (node (ref "U3") (pin "3") (pinfunction "C1_3") (pintype "output"))
    )
    (net (code "92") (name "unconnected-(U3-CN-Pad4)") (class "Default")
      (node (ref "U3") (pin "4") (pinfunction "CN_4") (pintype "output"))
    )
  )
)
